# RTI-Dome-Shutter-RP2040.net
KiCad netlist of a schematic drawn in EAGLE
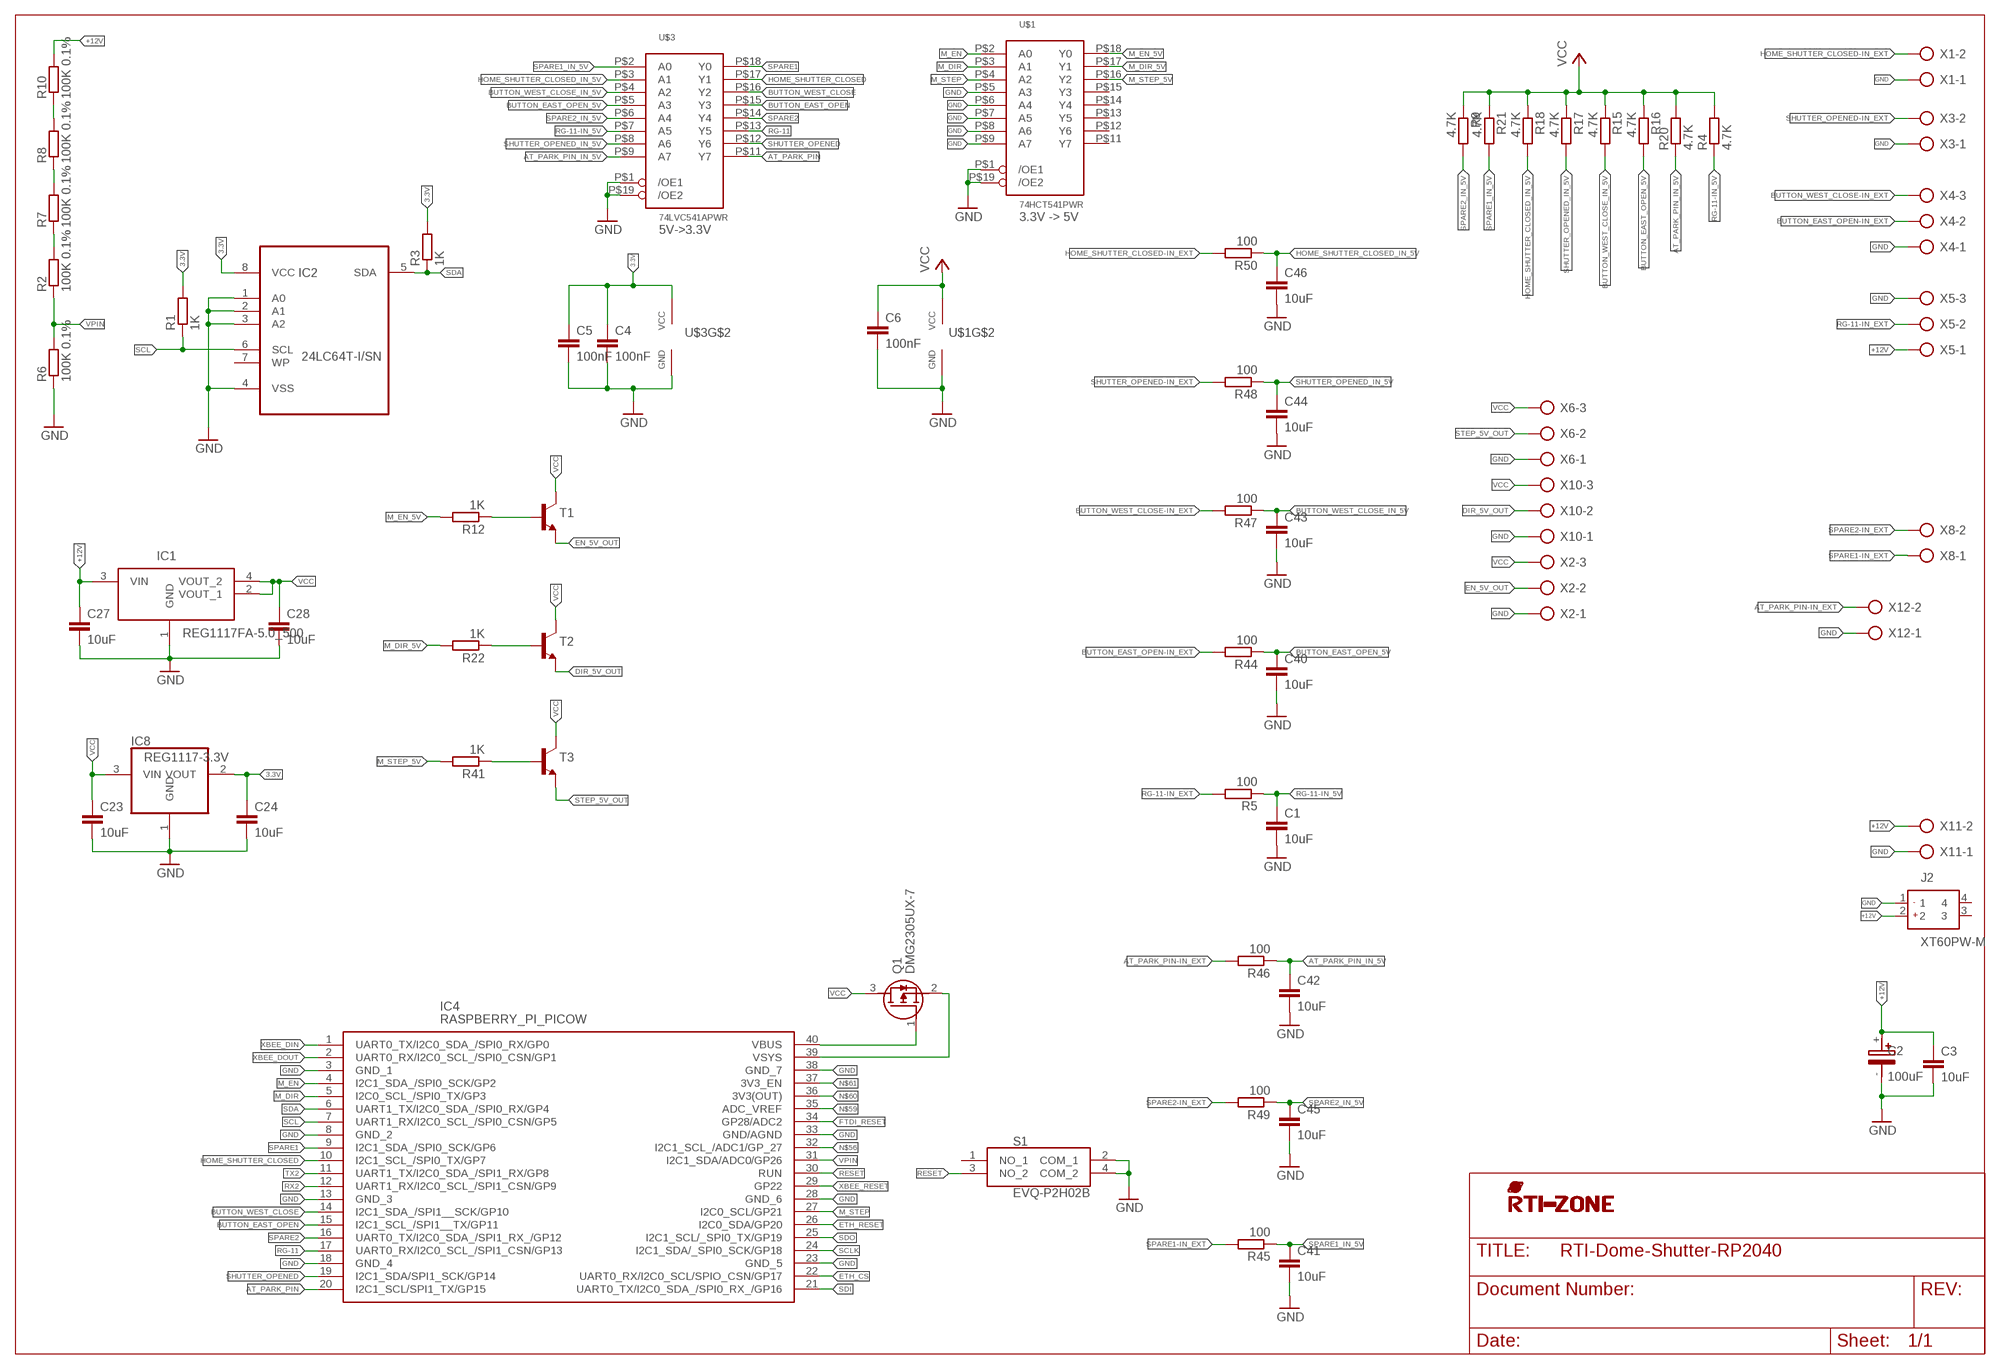
[diagram p0: schematic, sheet 1]

(export (version "E")
  (design (tool "Eeschema 10.0.6"))
  (components
    (comp (ref "C1")
      (value "10uF")
      (footprint "eagle-import:C0603")
      (fields (field (name "MPN") "CC0805KKX5R8BB106"))
      (libsource (lib "eagle-import") (part "C-EU'0603'"))
    )
    (comp (ref "C2")
      (value "100uF")
      (footprint "eagle-import:UD-10X10_NICHICON")
      (fields (field (name "MPN") "MAL215099804E3"))
      (libsource (lib "eagle-import") (part "MAL215099804E3{dblquote}{dblquote}"))
    )
    (comp (ref "C3")
      (value "10uF")
      (footprint "eagle-import:C0603")
      (fields (field (name "MPN") "CC0805KKX5R8BB106"))
      (libsource (lib "eagle-import") (part "C-EU'0603'"))
    )
    (comp (ref "C4")
      (value "100nF")
      (footprint "eagle-import:C0603")
      (fields (field (name "MPN") "0805YD104KAT2A"))
      (libsource (lib "eagle-import") (part "C-EU'0603'"))
    )
    (comp (ref "C5")
      (value "100nF")
      (footprint "eagle-import:C0603")
      (fields (field (name "MPN") "0805YD104KAT2A"))
      (libsource (lib "eagle-import") (part "C-EU'0603'"))
    )
    (comp (ref "C6")
      (value "100nF")
      (footprint "eagle-import:C0603")
      (fields (field (name "MPN") "0805YD104KAT2A"))
      (libsource (lib "eagle-import") (part "C-EU'0603'"))
    )
    (comp (ref "C23")
      (value "10uF")
      (footprint "eagle-import:C0603")
      (fields (field (name "MPN") "CC0805KKX5R8BB106"))
      (libsource (lib "eagle-import") (part "C-EU'0603'"))
    )
    (comp (ref "C24")
      (value "10uF")
      (footprint "eagle-import:C0603")
      (fields (field (name "MPN") "CC0805KKX5R8BB106"))
      (libsource (lib "eagle-import") (part "C-EU'0603'"))
    )
    (comp (ref "C27")
      (value "10uF")
      (footprint "eagle-import:C0603")
      (fields (field (name "MPN") "CC0805KKX5R8BB106"))
      (libsource (lib "eagle-import") (part "C-EU'0603'"))
    )
    (comp (ref "C28")
      (value "10uF")
      (footprint "eagle-import:C0603")
      (fields (field (name "MPN") "CC0805KKX5R8BB106"))
      (libsource (lib "eagle-import") (part "C-EU'0603'"))
    )
    (comp (ref "C40")
      (value "10uF")
      (footprint "eagle-import:C0603")
      (fields (field (name "MPN") "CC0805KKX5R8BB106"))
      (libsource (lib "eagle-import") (part "C-EU'0603'"))
    )
    (comp (ref "C41")
      (value "10uF")
      (footprint "eagle-import:C0603")
      (fields (field (name "MPN") "CC0805KKX5R8BB106"))
      (libsource (lib "eagle-import") (part "C-EU'0603'"))
    )
    (comp (ref "C42")
      (value "10uF")
      (footprint "eagle-import:C0603")
      (fields (field (name "MPN") "CC0805KKX5R8BB106"))
      (libsource (lib "eagle-import") (part "C-EU'0603'"))
    )
    (comp (ref "C43")
      (value "10uF")
      (footprint "eagle-import:C0603")
      (fields (field (name "MPN") "CC0805KKX5R8BB106"))
      (libsource (lib "eagle-import") (part "C-EU'0603'"))
    )
    (comp (ref "C44")
      (value "10uF")
      (footprint "eagle-import:C0603")
      (fields (field (name "MPN") "CC0805KKX5R8BB106"))
      (libsource (lib "eagle-import") (part "C-EU'0603'"))
    )
    (comp (ref "C45")
      (value "10uF")
      (footprint "eagle-import:C0603")
      (fields (field (name "MPN") "CC0805KKX5R8BB106"))
      (libsource (lib "eagle-import") (part "C-EU'0603'"))
    )
    (comp (ref "C46")
      (value "10uF")
      (footprint "eagle-import:C0603")
      (fields (field (name "MPN") "CC0805KKX5R8BB106"))
      (libsource (lib "eagle-import") (part "C-EU'0603'"))
    )
    (comp (ref "IC1")
      (value "REG1117FA-5.0_500")
      (footprint "eagle-import:REG1117FA50500")
      (fields
        (field (name "ARROW_PART_NUMBER") "REG1117FA-5.0/500")
        (field (name "MOUSER_PART_NUMBER") "595-REG1117FA50/500")
      )
      (libsource (lib "eagle-import") (part "REG1117FA-5.0_500"))
    )
    (comp (ref "IC2")
      (value "24LC64T-I/SN")
      (footprint "eagle-import:SOIC127P600X175-8N")
      (libsource (lib "eagle-import") (part "24LC64T-I/SN"))
    )
    (comp (ref "IC4")
      (value "RASPBERRY_PI_PICOW")
      (footprint "eagle-import:RASPBERRYPIPICO-W")
      (libsource (lib "eagle-import") (part "RASPBERRY_PI_PICOW"))
    )
    (comp (ref "IC8")
      (value "REG1117-3.3V")
      (footprint "eagle-import:SOT223")
      (fields (field (name "MPN") "REG1117") (field (name "MPN_1") "REG1117-3.3/2K5"))
      (libsource (lib "eagle-import") (part "REG1117"))
    )
    (comp (ref "J2")
      (value "XT60PW-M")
      (footprint "eagle-import:XT60PWM")
      (libsource (lib "eagle-import") (part "XT60PW-M"))
    )
    (comp (ref "Q1")
      (value "DMG2305UX-7")
      (footprint "eagle-import:SOT96P240X115-3N")
      (fields (field (name "MOUSER_PART_NUMBER") "621-DMG2305UX-7"))
      (libsource (lib "eagle-import") (part "DMG2305UX-7"))
    )
    (comp (ref "R1")
      (value "1K")
      (footprint "eagle-import:R0603")
      (fields (field (name "MPN") "RT0805FRE071KL"))
      (libsource (lib "eagle-import") (part "R-EU'0603'"))
    )
    (comp (ref "R2")
      (value "100K 0.1%")
      (footprint "eagle-import:R0603")
      (fields (field (name "MPN") "AT0805BRD07100KL"))
      (libsource (lib "eagle-import") (part "R-EU'0603'"))
    )
    (comp (ref "R3")
      (value "1K")
      (footprint "eagle-import:R0603")
      (fields (field (name "MPN") "RT0805FRE071KL"))
      (libsource (lib "eagle-import") (part "R-EU'0603'"))
    )
    (comp (ref "R4")
      (value "4.7K")
      (footprint "eagle-import:R0603")
      (fields (field (name "MPN") "RT0805FRE074K7L"))
      (libsource (lib "eagle-import") (part "R-EU'0603'"))
    )
    (comp (ref "R5")
      (value "100")
      (footprint "eagle-import:R0603")
      (fields (field (name "MPN") "RT0805FRD07100RL"))
      (libsource (lib "eagle-import") (part "R-EU'0603'"))
    )
    (comp (ref "R6")
      (value "100K 0.1%")
      (footprint "eagle-import:R0603")
      (fields (field (name "MPN") "AT0805BRD07100KL"))
      (libsource (lib "eagle-import") (part "R-EU'0603'"))
    )
    (comp (ref "R7")
      (value "100K 0.1%")
      (footprint "eagle-import:R0603")
      (fields (field (name "MPN") "AT0805BRD07100KL"))
      (libsource (lib "eagle-import") (part "R-EU'0603'"))
    )
    (comp (ref "R8")
      (value "100K 0.1%")
      (footprint "eagle-import:R0603")
      (fields (field (name "MPN") "AT0805BRD07100KL"))
      (libsource (lib "eagle-import") (part "R-EU'0603'"))
    )
    (comp (ref "R9")
      (value "4.7K")
      (footprint "eagle-import:R0603")
      (fields (field (name "MPN") "RT0805FRE074K7L"))
      (libsource (lib "eagle-import") (part "R-EU'0603'"))
    )
    (comp (ref "R10")
      (value "100K 0.1%")
      (footprint "eagle-import:R0603")
      (fields (field (name "MPN") "AT0805BRD07100KL"))
      (libsource (lib "eagle-import") (part "R-EU'0603'"))
    )
    (comp (ref "R12")
      (value "1K")
      (footprint "eagle-import:R0603")
      (fields (field (name "MPN") "RT0805FRE074K7L"))
      (libsource (lib "eagle-import") (part "R-EU'0603'"))
    )
    (comp (ref "R15")
      (value "4.7K")
      (footprint "eagle-import:R0603")
      (fields (field (name "MPN") "RT0805FRE074K7L"))
      (libsource (lib "eagle-import") (part "R-EU'0603'"))
    )
    (comp (ref "R16")
      (value "4.7K")
      (footprint "eagle-import:R0603")
      (fields (field (name "MPN") "RT0805FRE074K7L"))
      (libsource (lib "eagle-import") (part "R-EU'0603'"))
    )
    (comp (ref "R17")
      (value "4.7K")
      (footprint "eagle-import:R0603")
      (fields (field (name "MPN") "RT0805FRE074K7L"))
      (libsource (lib "eagle-import") (part "R-EU'0603'"))
    )
    (comp (ref "R18")
      (value "4.7K")
      (footprint "eagle-import:R0603")
      (fields (field (name "MPN") "RT0805FRE074K7L"))
      (libsource (lib "eagle-import") (part "R-EU'0603'"))
    )
    (comp (ref "R20")
      (value "4.7K")
      (footprint "eagle-import:R0603")
      (fields (field (name "MPN") "RT0805FRE074K7L"))
      (libsource (lib "eagle-import") (part "R-EU'0603'"))
    )
    (comp (ref "R21")
      (value "4.7K")
      (footprint "eagle-import:R0603")
      (fields (field (name "MPN") "RT0805FRE074K7L"))
      (libsource (lib "eagle-import") (part "R-EU'0603'"))
    )
    (comp (ref "R22")
      (value "1K")
      (footprint "eagle-import:R0603")
      (fields (field (name "MPN") "RT0805FRE074K7L"))
      (libsource (lib "eagle-import") (part "R-EU'0603'"))
    )
    (comp (ref "R41")
      (value "1K")
      (footprint "eagle-import:R0603")
      (fields (field (name "MPN") "RT0805FRE074K7L"))
      (libsource (lib "eagle-import") (part "R-EU'0603'"))
    )
    (comp (ref "R44")
      (value "100")
      (footprint "eagle-import:R0603")
      (fields (field (name "MPN") "RT0805FRD07100RL"))
      (libsource (lib "eagle-import") (part "R-EU'0603'"))
    )
    (comp (ref "R45")
      (value "100")
      (footprint "eagle-import:R0603")
      (fields (field (name "MPN") "RT0805FRD07100RL"))
      (libsource (lib "eagle-import") (part "R-EU'0603'"))
    )
    (comp (ref "R46")
      (value "100")
      (footprint "eagle-import:R0603")
      (fields (field (name "MPN") "RT0805FRD07100RL"))
      (libsource (lib "eagle-import") (part "R-EU'0603'"))
    )
    (comp (ref "R47")
      (value "100")
      (footprint "eagle-import:R0603")
      (fields (field (name "MPN") "RT0805FRD07100RL"))
      (libsource (lib "eagle-import") (part "R-EU'0603'"))
    )
    (comp (ref "R48")
      (value "100")
      (footprint "eagle-import:R0603")
      (fields (field (name "MPN") "RT0805FRD07100RL"))
      (libsource (lib "eagle-import") (part "R-EU'0603'"))
    )
    (comp (ref "R49")
      (value "100")
      (footprint "eagle-import:R0603")
      (fields (field (name "MPN") "RT0805FRD07100RL"))
      (libsource (lib "eagle-import") (part "R-EU'0603'"))
    )
    (comp (ref "R50")
      (value "100")
      (footprint "eagle-import:R0603")
      (fields (field (name "MPN") "RT0805FRD07100RL"))
      (libsource (lib "eagle-import") (part "R-EU'0603'"))
    )
    (comp (ref "S1")
      (value "EVQ-P2H02B")
      (footprint "eagle-import:EVQP2H02B")
      (fields (field (name "MOUSER_PART_NUMBER") "667-EVQ-P2H02B"))
      (libsource (lib "eagle-import") (part "EVQ-P2H02B"))
    )
    (comp (ref "T1")
      (value "MMBT3904LT1-NPN-SOT23-BEC")
      (footprint "eagle-import:SOT23-BEC")
      (libsource (lib "eagle-import") (part "-NPN-SOT23-BECMMBT3904LT1"))
    )
    (comp (ref "T2")
      (value "MMBT3904LT1-NPN-SOT23-BEC")
      (footprint "eagle-import:SOT23-BEC")
      (libsource (lib "eagle-import") (part "-NPN-SOT23-BECMMBT3904LT1"))
    )
    (comp (ref "T3")
      (value "MMBT3904LT1-NPN-SOT23-BEC")
      (footprint "eagle-import:SOT23-BEC")
      (libsource (lib "eagle-import") (part "-NPN-SOT23-BECMMBT3904LT1"))
    )
    (comp (ref "U$1")
      (value "74HCT541PWR")
      (footprint "eagle-import:TSSOP20")
      (libsource (lib "eagle-import") (part "74541B"))
    )
    (comp (ref "U$3")
      (value "74LVC541APWR")
      (footprint "eagle-import:TSSOP20")
      (libsource (lib "eagle-import") (part "74541B"))
    )
    (comp (ref "U$4")
      (value "RTI-LOGO_BIG")
      (footprint "eagle-import:LOGO_BIG")
      (libsource (lib "eagle-import") (part "RTI-LOGO_BIG"))
    )
    (comp (ref "X1")
      (value "AK500/2")
      (footprint "eagle-import:AK500_2")
      (fields (field (name "MPN") "691101710002"))
      (libsource (lib "eagle-import") (part "AK500/2"))
    )
    (comp (ref "X2")
      (value "AK500/3")
      (footprint "eagle-import:AK500_3")
      (libsource (lib "eagle-import") (part "AK500/3"))
    )
    (comp (ref "X3")
      (value "AK500/2")
      (footprint "eagle-import:AK500_2")
      (fields (field (name "MPN") "691101710002"))
      (libsource (lib "eagle-import") (part "AK500/2"))
    )
    (comp (ref "X4")
      (value "AK500/3")
      (footprint "eagle-import:AK500_3")
      (fields (field (name "MPN") "691101710003"))
      (libsource (lib "eagle-import") (part "AK500/3"))
    )
    (comp (ref "X5")
      (value "AK500/3")
      (footprint "eagle-import:AK500_3")
      (fields (field (name "MPN") "691101710003"))
      (libsource (lib "eagle-import") (part "AK500/3"))
    )
    (comp (ref "X6")
      (value "AK500/3")
      (footprint "eagle-import:AK500_3")
      (libsource (lib "eagle-import") (part "AK500/3"))
    )
    (comp (ref "X8")
      (value "AK500/2")
      (footprint "eagle-import:AK500_2")
      (fields (field (name "MPN") "691101710002"))
      (libsource (lib "eagle-import") (part "AK500/2"))
    )
    (comp (ref "X10")
      (value "AK500/3")
      (footprint "eagle-import:AK500_3")
      (libsource (lib "eagle-import") (part "AK500/3"))
    )
    (comp (ref "X11")
      (value "AK500/2")
      (footprint "eagle-import:AK500_2")
      (fields (field (name "MPN") "691101710002"))
      (libsource (lib "eagle-import") (part "AK500/2"))
    )
    (comp (ref "X12")
      (value "AK500/2")
      (footprint "eagle-import:AK500_2")
      (fields (field (name "MPN") "691101710002"))
      (libsource (lib "eagle-import") (part "AK500/2"))
    )
  )
  (nets
    (net (code "1") (name "+12V") (class "Default")
      (node (ref "C2") (pin "+") (pinfunction "+_+") (pintype "bidirectional"))
      (node (ref "C27") (pin "1") (pinfunction "1_1") (pintype "passive"))
      (node (ref "C3") (pin "1") (pinfunction "1_1") (pintype "passive"))
      (node (ref "IC1") (pin "3") (pinfunction "VIN_3") (pintype "bidirectional"))
      (node (ref "J2") (pin "2") (pinfunction "2_2") (pintype "bidirectional"))
      (node (ref "R10") (pin "2") (pinfunction "2_2") (pintype "passive"))
      (node (ref "X11") (pin "2") (pinfunction "KL_2") (pintype "passive"))
      (node (ref "X5") (pin "1") (pinfunction "KL_1") (pintype "passive"))
    )
    (net (code "2") (name "3.3V") (class "Default")
      (node (ref "C24") (pin "1") (pinfunction "1_1") (pintype "passive"))
      (node (ref "C4") (pin "1") (pinfunction "1_1") (pintype "passive"))
      (node (ref "C5") (pin "1") (pinfunction "1_1") (pintype "passive"))
      (node (ref "IC2") (pin "8") (pinfunction "VCC_8") (pintype "power_in"))
      (node (ref "IC8") (pin "2") (pinfunction "VOUT_2") (pintype "output"))
      (node (ref "R1") (pin "2") (pinfunction "2_2") (pintype "passive"))
      (node (ref "R3") (pin "2") (pinfunction "2_2") (pintype "passive"))
      (node (ref "U$3") (pin "P$20") (pinfunction "VCC_P$20") (pintype "power_in"))
    )
    (net (code "3") (name "AT_PARK_PIN") (class "Default")
      (node (ref "IC4") (pin "20") (pinfunction "I2C1_SCL/SPI1_TX/GP15_20") (pintype "bidirectional"))
      (node (ref "U$3") (pin "P$11") (pinfunction "Y7_P$11") (pintype "output"))
    )
    (net (code "4") (name "AT_PARK_PIN-IN_EXT") (class "Default")
      (node (ref "R46") (pin "2") (pinfunction "2_2") (pintype "passive"))
      (node (ref "X12") (pin "2") (pinfunction "KL_2") (pintype "passive"))
    )
    (net (code "5") (name "AT_PARK_PIN_IN_5V") (class "Default")
      (node (ref "C42") (pin "1") (pinfunction "1_1") (pintype "passive"))
      (node (ref "R20") (pin "1") (pinfunction "1_1") (pintype "passive"))
      (node (ref "R46") (pin "1") (pinfunction "1_1") (pintype "passive"))
      (node (ref "U$3") (pin "P$9") (pinfunction "A7_P$9") (pintype "input"))
    )
    (net (code "6") (name "BUTTON_EAST_OPEN") (class "Default")
      (node (ref "IC4") (pin "15") (pinfunction "I2C1_SCL_/SPI1__TX/GP11_15") (pintype "bidirectional"))
      (node (ref "U$3") (pin "P$15") (pinfunction "Y3_P$15") (pintype "output"))
    )
    (net (code "7") (name "BUTTON_EAST_OPEN-IN_EXT") (class "Default")
      (node (ref "R44") (pin "2") (pinfunction "2_2") (pintype "passive"))
      (node (ref "X4") (pin "2") (pinfunction "KL_2") (pintype "passive"))
    )
    (net (code "8") (name "BUTTON_EAST_OPEN_5V") (class "Default")
      (node (ref "C40") (pin "1") (pinfunction "1_1") (pintype "passive"))
      (node (ref "R16") (pin "2") (pinfunction "2_2") (pintype "passive"))
      (node (ref "R44") (pin "1") (pinfunction "1_1") (pintype "passive"))
      (node (ref "U$3") (pin "P$5") (pinfunction "A3_P$5") (pintype "input"))
    )
    (net (code "9") (name "BUTTON_WEST_CLOSE") (class "Default")
      (node (ref "IC4") (pin "14") (pinfunction "I2C1_SDA_/SPI1__SCK/GP10_14") (pintype "bidirectional"))
      (node (ref "U$3") (pin "P$16") (pinfunction "Y2_P$16") (pintype "output"))
    )
    (net (code "10") (name "BUTTON_WEST_CLOSE-IN_EXT") (class "Default")
      (node (ref "R47") (pin "2") (pinfunction "2_2") (pintype "passive"))
      (node (ref "X4") (pin "3") (pinfunction "KL_3") (pintype "passive"))
    )
    (net (code "11") (name "BUTTON_WEST_CLOSE_IN_5V") (class "Default")
      (node (ref "C43") (pin "1") (pinfunction "1_1") (pintype "passive"))
      (node (ref "R15") (pin "2") (pinfunction "2_2") (pintype "passive"))
      (node (ref "R47") (pin "1") (pinfunction "1_1") (pintype "passive"))
      (node (ref "U$3") (pin "P$4") (pinfunction "A2_P$4") (pintype "input"))
    )
    (net (code "12") (name "DIR_5V_OUT") (class "Default")
      (node (ref "T2") (pin "E") (pinfunction "E_E") (pintype "passive"))
      (node (ref "X10") (pin "2") (pinfunction "KL_2") (pintype "passive"))
    )
    (net (code "13") (name "EN_5V_OUT") (class "Default")
      (node (ref "T1") (pin "E") (pinfunction "E_E") (pintype "passive"))
      (node (ref "X2") (pin "2") (pinfunction "KL_2") (pintype "passive"))
    )
    (net (code "14") (name "ETH_CS") (class "Default")
      (node (ref "IC4") (pin "22") (pinfunction "UART0_RX/I2C0_SCL/SPIO_CSN/GP17_22") (pintype "bidirectional"))
    )
    (net (code "15") (name "ETH_RESET") (class "Default")
      (node (ref "IC4") (pin "26") (pinfunction "I2C0_SDA/GP20_26") (pintype "bidirectional"))
    )
    (net (code "16") (name "FTDI_RESET") (class "Default")
      (node (ref "IC4") (pin "34") (pinfunction "GP28/ADC2_34") (pintype "bidirectional"))
    )
    (net (code "17") (name "GND") (class "Default")
      (node (ref "C1") (pin "2") (pinfunction "2_2") (pintype "passive"))
      (node (ref "C2") (pin "-") (pinfunction "-_-") (pintype "bidirectional"))
      (node (ref "C23") (pin "2") (pinfunction "2_2") (pintype "passive"))
      (node (ref "C24") (pin "2") (pinfunction "2_2") (pintype "passive"))
      (node (ref "C27") (pin "2") (pinfunction "2_2") (pintype "passive"))
      (node (ref "C28") (pin "2") (pinfunction "2_2") (pintype "passive"))
      (node (ref "C3") (pin "2") (pinfunction "2_2") (pintype "passive"))
      (node (ref "C4") (pin "2") (pinfunction "2_2") (pintype "passive"))
      (node (ref "C40") (pin "2") (pinfunction "2_2") (pintype "passive"))
      (node (ref "C41") (pin "2") (pinfunction "2_2") (pintype "passive"))
      (node (ref "C42") (pin "2") (pinfunction "2_2") (pintype "passive"))
      (node (ref "C43") (pin "2") (pinfunction "2_2") (pintype "passive"))
      (node (ref "C44") (pin "2") (pinfunction "2_2") (pintype "passive"))
      (node (ref "C45") (pin "2") (pinfunction "2_2") (pintype "passive"))
      (node (ref "C46") (pin "2") (pinfunction "2_2") (pintype "passive"))
      (node (ref "C5") (pin "2") (pinfunction "2_2") (pintype "passive"))
      (node (ref "C6") (pin "2") (pinfunction "2_2") (pintype "passive"))
      (node (ref "IC1") (pin "1") (pinfunction "GND_1") (pintype "bidirectional"))
      (node (ref "IC2") (pin "1") (pinfunction "A0_1") (pintype "input"))
      (node (ref "IC2") (pin "2") (pinfunction "A1_2") (pintype "input"))
      (node (ref "IC2") (pin "3") (pinfunction "A2_3") (pintype "input"))
      (node (ref "IC2") (pin "4") (pinfunction "VSS_4") (pintype "passive"))
      (node (ref "IC4") (pin "13") (pinfunction "GND_3_13") (pintype "bidirectional"))
      (node (ref "IC4") (pin "18") (pinfunction "GND_4_18") (pintype "bidirectional"))
      (node (ref "IC4") (pin "23") (pinfunction "GND_5_23") (pintype "bidirectional"))
      (node (ref "IC4") (pin "28") (pinfunction "GND_6_28") (pintype "bidirectional"))
      (node (ref "IC4") (pin "3") (pinfunction "GND_1_3") (pintype "bidirectional"))
      (node (ref "IC4") (pin "33") (pinfunction "GND/AGND_33") (pintype "bidirectional"))
      (node (ref "IC4") (pin "38") (pinfunction "GND_7_38") (pintype "bidirectional"))
      (node (ref "IC4") (pin "8") (pinfunction "GND_2_8") (pintype "bidirectional"))
      (node (ref "IC8") (pin "1") (pinfunction "GND_1") (pintype "power_in"))
      (node (ref "J2") (pin "1") (pinfunction "1_1") (pintype "bidirectional"))
      (node (ref "R6") (pin "1") (pinfunction "1_1") (pintype "passive"))
      (node (ref "S1") (pin "2") (pinfunction "COM_1_2") (pintype "bidirectional"))
      (node (ref "S1") (pin "4") (pinfunction "COM_2_4") (pintype "bidirectional"))
      (node (ref "U$1") (pin "P$1") (pinfunction "/OE1_P$1") (pintype "input"))
      (node (ref "U$1") (pin "P$10") (pinfunction "GND_P$10") (pintype "power_in"))
      (node (ref "U$1") (pin "P$19") (pinfunction "/OE2_P$19") (pintype "input"))
      (node (ref "U$1") (pin "P$5") (pinfunction "A3_P$5") (pintype "input"))
      (node (ref "U$1") (pin "P$6") (pinfunction "A4_P$6") (pintype "input"))
      (node (ref "U$1") (pin "P$7") (pinfunction "A5_P$7") (pintype "input"))
      (node (ref "U$1") (pin "P$8") (pinfunction "A6_P$8") (pintype "input"))
      (node (ref "U$1") (pin "P$9") (pinfunction "A7_P$9") (pintype "input"))
      (node (ref "U$3") (pin "P$1") (pinfunction "/OE1_P$1") (pintype "input"))
      (node (ref "U$3") (pin "P$10") (pinfunction "GND_P$10") (pintype "power_in"))
      (node (ref "U$3") (pin "P$19") (pinfunction "/OE2_P$19") (pintype "input"))
      (node (ref "X1") (pin "1") (pinfunction "KL_1") (pintype "passive"))
      (node (ref "X10") (pin "1") (pinfunction "KL_1") (pintype "passive"))
      (node (ref "X11") (pin "1") (pinfunction "KL_1") (pintype "passive"))
      (node (ref "X12") (pin "1") (pinfunction "KL_1") (pintype "passive"))
      (node (ref "X2") (pin "1") (pinfunction "KL_1") (pintype "passive"))
      (node (ref "X3") (pin "1") (pinfunction "KL_1") (pintype "passive"))
      (node (ref "X4") (pin "1") (pinfunction "KL_1") (pintype "passive"))
      (node (ref "X5") (pin "3") (pinfunction "KL_3") (pintype "passive"))
      (node (ref "X6") (pin "1") (pinfunction "KL_1") (pintype "passive"))
    )
    (net (code "18") (name "HOME_SHUTTER_CLOSED") (class "Default")
      (node (ref "IC4") (pin "10") (pinfunction "I2C1_SCL_/SPI0_TX/GP7_10") (pintype "bidirectional"))
      (node (ref "U$3") (pin "P$17") (pinfunction "Y1_P$17") (pintype "output"))
    )
    (net (code "19") (name "HOME_SHUTTER_CLOSED-IN_EXT") (class "Default")
      (node (ref "R50") (pin "2") (pinfunction "2_2") (pintype "passive"))
      (node (ref "X1") (pin "2") (pinfunction "KL_2") (pintype "passive"))
    )
    (net (code "20") (name "HOME_SHUTTER_CLOSED_IN_5V") (class "Default")
      (node (ref "C46") (pin "1") (pinfunction "1_1") (pintype "passive"))
      (node (ref "R18") (pin "2") (pinfunction "2_2") (pintype "passive"))
      (node (ref "R50") (pin "1") (pinfunction "1_1") (pintype "passive"))
      (node (ref "U$3") (pin "P$3") (pinfunction "A1_P$3") (pintype "input"))
    )
    (net (code "21") (name "M_DIR") (class "Default")
      (node (ref "IC4") (pin "5") (pinfunction "I2C0_SCL_/SPI0_TX/GP3_5") (pintype "bidirectional"))
      (node (ref "U$1") (pin "P$3") (pinfunction "A1_P$3") (pintype "input"))
    )
    (net (code "22") (name "M_DIR_5V") (class "Default")
      (node (ref "R22") (pin "2") (pinfunction "2_2") (pintype "passive"))
      (node (ref "U$1") (pin "P$17") (pinfunction "Y1_P$17") (pintype "output"))
    )
    (net (code "23") (name "M_EN") (class "Default")
      (node (ref "IC4") (pin "4") (pinfunction "I2C1_SDA_/SPI0_SCK/GP2_4") (pintype "bidirectional"))
      (node (ref "U$1") (pin "P$2") (pinfunction "A0_P$2") (pintype "input"))
    )
    (net (code "24") (name "M_EN_5V") (class "Default")
      (node (ref "R12") (pin "2") (pinfunction "2_2") (pintype "passive"))
      (node (ref "U$1") (pin "P$18") (pinfunction "Y0_P$18") (pintype "output"))
    )
    (net (code "25") (name "M_STEP") (class "Default")
      (node (ref "IC4") (pin "27") (pinfunction "I2C0_SCL/GP21_27") (pintype "bidirectional"))
      (node (ref "U$1") (pin "P$4") (pinfunction "A2_P$4") (pintype "input"))
    )
    (net (code "26") (name "M_STEP_5V") (class "Default")
      (node (ref "R41") (pin "2") (pinfunction "2_2") (pintype "passive"))
      (node (ref "U$1") (pin "P$16") (pinfunction "Y2_P$16") (pintype "output"))
    )
    (net (code "27") (name "N$56") (class "Default")
      (node (ref "IC4") (pin "32") (pinfunction "I2C1_SCL_/ADC1/GP_27_32") (pintype "bidirectional"))
    )
    (net (code "28") (name "N$59") (class "Default")
      (node (ref "IC4") (pin "35") (pinfunction "ADC_VREF_35") (pintype "bidirectional"))
    )
    (net (code "29") (name "N$60") (class "Default")
      (node (ref "IC4") (pin "36") (pinfunction "3V3(OUT)_36") (pintype "bidirectional"))
    )
    (net (code "30") (name "N$61") (class "Default")
      (node (ref "IC4") (pin "37") (pinfunction "3V3_EN_37") (pintype "bidirectional"))
    )
    (net (code "31") (name "Net-(IC4-VBUS)") (class "Default")
      (node (ref "IC4") (pin "40") (pinfunction "VBUS_40") (pintype "bidirectional"))
      (node (ref "Q1") (pin "1") (pinfunction "G_1") (pintype "bidirectional"))
    )
    (net (code "32") (name "Net-(IC4-VSYS)") (class "Default")
      (node (ref "IC4") (pin "39") (pinfunction "VSYS_39") (pintype "bidirectional"))
      (node (ref "Q1") (pin "2") (pinfunction "S_2") (pintype "bidirectional"))
    )
    (net (code "33") (name "Net-(R2-Pad2)") (class "Default")
      (node (ref "R2") (pin "2") (pinfunction "2_2") (pintype "passive"))
      (node (ref "R7") (pin "1") (pinfunction "1_1") (pintype "passive"))
    )
    (net (code "34") (name "Net-(R7-Pad2)") (class "Default")
      (node (ref "R7") (pin "2") (pinfunction "2_2") (pintype "passive"))
      (node (ref "R8") (pin "1") (pinfunction "1_1") (pintype "passive"))
    )
    (net (code "35") (name "Net-(R10-Pad1)") (class "Default")
      (node (ref "R10") (pin "1") (pinfunction "1_1") (pintype "passive"))
      (node (ref "R8") (pin "2") (pinfunction "2_2") (pintype "passive"))
    )
    (net (code "36") (name "Net-(R12-Pad1)") (class "Default")
      (node (ref "R12") (pin "1") (pinfunction "1_1") (pintype "passive"))
      (node (ref "T1") (pin "B") (pinfunction "B_B") (pintype "passive"))
    )
    (net (code "37") (name "Net-(R22-Pad1)") (class "Default")
      (node (ref "R22") (pin "1") (pinfunction "1_1") (pintype "passive"))
      (node (ref "T2") (pin "B") (pinfunction "B_B") (pintype "passive"))
    )
    (net (code "38") (name "Net-(R41-Pad1)") (class "Default")
      (node (ref "R41") (pin "1") (pinfunction "1_1") (pintype "passive"))
      (node (ref "T3") (pin "B") (pinfunction "B_B") (pintype "passive"))
    )
    (net (code "39") (name "RESET") (class "Default")
      (node (ref "IC4") (pin "30") (pinfunction "RUN_30") (pintype "bidirectional"))
      (node (ref "S1") (pin "3") (pinfunction "NO_2_3") (pintype "bidirectional"))
    )
    (net (code "40") (name "RG-11") (class "Default")
      (node (ref "IC4") (pin "17") (pinfunction "UART0_RX/I2C0_SCL_/SPI1_CSN/GP13_17") (pintype "bidirectional"))
      (node (ref "U$3") (pin "P$13") (pinfunction "Y5_P$13") (pintype "output"))
    )
    (net (code "41") (name "RG-11-IN_5V") (class "Default")
      (node (ref "C1") (pin "1") (pinfunction "1_1") (pintype "passive"))
      (node (ref "R4") (pin "1") (pinfunction "1_1") (pintype "passive"))
      (node (ref "R5") (pin "1") (pinfunction "1_1") (pintype "passive"))
      (node (ref "U$3") (pin "P$7") (pinfunction "A5_P$7") (pintype "input"))
    )
    (net (code "42") (name "RG-11-IN_EXT") (class "Default")
      (node (ref "R5") (pin "2") (pinfunction "2_2") (pintype "passive"))
      (node (ref "X5") (pin "2") (pinfunction "KL_2") (pintype "passive"))
    )
    (net (code "43") (name "RX2") (class "Default")
      (node (ref "IC4") (pin "12") (pinfunction "UART1_RX/I2C0_SCL_/SPI1_CSN/GP9_12") (pintype "bidirectional"))
    )
    (net (code "44") (name "SCL") (class "Default")
      (node (ref "IC2") (pin "6") (pinfunction "SCL_6") (pintype "input"))
      (node (ref "IC4") (pin "7") (pinfunction "UART1_RX/I2C0_SCL_/SPI0_CSN/GP5_7") (pintype "bidirectional"))
      (node (ref "R1") (pin "1") (pinfunction "1_1") (pintype "passive"))
    )
    (net (code "45") (name "SCLK") (class "Default")
      (node (ref "IC4") (pin "24") (pinfunction "I2C1_SDA/_SPI0_SCK/GP18_24") (pintype "bidirectional"))
    )
    (net (code "46") (name "SDA") (class "Default")
      (node (ref "IC2") (pin "5") (pinfunction "SDA_5") (pintype "bidirectional"))
      (node (ref "IC4") (pin "6") (pinfunction "UART1_TX/I2C0_SDA_/SPI0_RX/GP4_6") (pintype "bidirectional"))
      (node (ref "R3") (pin "1") (pinfunction "1_1") (pintype "passive"))
    )
    (net (code "47") (name "SDI") (class "Default")
      (node (ref "IC4") (pin "21") (pinfunction "UART0_TX/I2C0_SDA_/SPI0_RX_/GP16_21") (pintype "bidirectional"))
    )
    (net (code "48") (name "SDO") (class "Default")
      (node (ref "IC4") (pin "25") (pinfunction "I2C1_SCL/_SPI0_TX/GP19_25") (pintype "bidirectional"))
    )
    (net (code "49") (name "SHUTTER_OPENED") (class "Default")
      (node (ref "IC4") (pin "19") (pinfunction "I2C1_SDA/SPI1_SCK/GP14_19") (pintype "bidirectional"))
      (node (ref "U$3") (pin "P$12") (pinfunction "Y6_P$12") (pintype "output"))
    )
    (net (code "50") (name "SHUTTER_OPENED-IN_EXT") (class "Default")
      (node (ref "R48") (pin "2") (pinfunction "2_2") (pintype "passive"))
      (node (ref "X3") (pin "2") (pinfunction "KL_2") (pintype "passive"))
    )
    (net (code "51") (name "SHUTTER_OPENED_IN_5V") (class "Default")
      (node (ref "C44") (pin "1") (pinfunction "1_1") (pintype "passive"))
      (node (ref "R17") (pin "2") (pinfunction "2_2") (pintype "passive"))
      (node (ref "R48") (pin "1") (pinfunction "1_1") (pintype "passive"))
      (node (ref "U$3") (pin "P$8") (pinfunction "A6_P$8") (pintype "input"))
    )
    (net (code "52") (name "SPARE1") (class "Default")
      (node (ref "IC4") (pin "9") (pinfunction "I2C1_SDA_/SPI0_SCK/GP6_9") (pintype "bidirectional"))
      (node (ref "U$3") (pin "P$18") (pinfunction "Y0_P$18") (pintype "output"))
    )
    (net (code "53") (name "SPARE1-IN_EXT") (class "Default")
      (node (ref "R45") (pin "2") (pinfunction "2_2") (pintype "passive"))
      (node (ref "X8") (pin "1") (pinfunction "KL_1") (pintype "passive"))
    )
    (net (code "54") (name "SPARE1_IN_5V") (class "Default")
      (node (ref "C41") (pin "1") (pinfunction "1_1") (pintype "passive"))
      (node (ref "R21") (pin "2") (pinfunction "2_2") (pintype "passive"))
      (node (ref "R45") (pin "1") (pinfunction "1_1") (pintype "passive"))
      (node (ref "U$3") (pin "P$2") (pinfunction "A0_P$2") (pintype "input"))
    )
    (net (code "55") (name "SPARE2") (class "Default")
      (node (ref "IC4") (pin "16") (pinfunction "UART0_TX/I2C0_SDA_/SPI1_RX_/GP12_16") (pintype "bidirectional"))
      (node (ref "U$3") (pin "P$14") (pinfunction "Y4_P$14") (pintype "output"))
    )
    (net (code "56") (name "SPARE2-IN_EXT") (class "Default")
      (node (ref "R49") (pin "2") (pinfunction "2_2") (pintype "passive"))
      (node (ref "X8") (pin "2") (pinfunction "KL_2") (pintype "passive"))
    )
    (net (code "57") (name "SPARE2_IN_5V") (class "Default")
      (node (ref "C45") (pin "1") (pinfunction "1_1") (pintype "passive"))
      (node (ref "R49") (pin "1") (pinfunction "1_1") (pintype "passive"))
      (node (ref "R9") (pin "2") (pinfunction "2_2") (pintype "passive"))
      (node (ref "U$3") (pin "P$6") (pinfunction "A4_P$6") (pintype "input"))
    )
    (net (code "58") (name "STEP_5V_OUT") (class "Default")
      (node (ref "T3") (pin "E") (pinfunction "E_E") (pintype "passive"))
      (node (ref "X6") (pin "2") (pinfunction "KL_2") (pintype "passive"))
    )
    (net (code "59") (name "TX2") (class "Default")
      (node (ref "IC4") (pin "11") (pinfunction "UART1_TX/I2C0_SDA_/SPI1_RX/GP8_11") (pintype "bidirectional"))
    )
    (net (code "60") (name "VCC") (class "Default")
      (node (ref "C23") (pin "1") (pinfunction "1_1") (pintype "passive"))
      (node (ref "C28") (pin "1") (pinfunction "1_1") (pintype "passive"))
      (node (ref "C6") (pin "1") (pinfunction "1_1") (pintype "passive"))
      (node (ref "IC1") (pin "2") (pinfunction "VOUT_1_2") (pintype "bidirectional"))
      (node (ref "IC1") (pin "4") (pinfunction "VOUT_2_4") (pintype "bidirectional"))
      (node (ref "IC8") (pin "3") (pinfunction "VIN_3") (pintype "input"))
      (node (ref "Q1") (pin "3") (pinfunction "D_3") (pintype "bidirectional"))
      (node (ref "R15") (pin "1") (pinfunction "1_1") (pintype "passive"))
      (node (ref "R16") (pin "1") (pinfunction "1_1") (pintype "passive"))
      (node (ref "R17") (pin "1") (pinfunction "1_1") (pintype "passive"))
      (node (ref "R18") (pin "1") (pinfunction "1_1") (pintype "passive"))
      (node (ref "R20") (pin "2") (pinfunction "2_2") (pintype "passive"))
      (node (ref "R21") (pin "1") (pinfunction "1_1") (pintype "passive"))
      (node (ref "R4") (pin "2") (pinfunction "2_2") (pintype "passive"))
      (node (ref "R9") (pin "1") (pinfunction "1_1") (pintype "passive"))
      (node (ref "T1") (pin "C") (pinfunction "C_C") (pintype "passive"))
      (node (ref "T2") (pin "C") (pinfunction "C_C") (pintype "passive"))
      (node (ref "T3") (pin "C") (pinfunction "C_C") (pintype "passive"))
      (node (ref "U$1") (pin "P$20") (pinfunction "VCC_P$20") (pintype "power_in"))
      (node (ref "X10") (pin "3") (pinfunction "KL_3") (pintype "passive"))
      (node (ref "X2") (pin "3") (pinfunction "KL_3") (pintype "passive"))
      (node (ref "X6") (pin "3") (pinfunction "KL_3") (pintype "passive"))
    )
    (net (code "61") (name "VPIN") (class "Default")
      (node (ref "IC4") (pin "31") (pinfunction "I2C1_SDA/ADC0/GP26_31") (pintype "bidirectional"))
      (node (ref "R2") (pin "1") (pinfunction "1_1") (pintype "passive"))
      (node (ref "R6") (pin "2") (pinfunction "2_2") (pintype "passive"))
    )
    (net (code "62") (name "XBEE_DIN") (class "Default")
      (node (ref "IC4") (pin "1") (pinfunction "UART0_TX/I2C0_SDA_/SPI0_RX/GP0_1") (pintype "bidirectional"))
    )
    (net (code "63") (name "XBEE_DOUT") (class "Default")
      (node (ref "IC4") (pin "2") (pinfunction "UART0_RX/I2C0_SCL_/SPI0_CSN/GP1_2") (pintype "bidirectional"))
    )
    (net (code "64") (name "XBEE_RESET") (class "Default")
      (node (ref "IC4") (pin "29") (pinfunction "GP22_29") (pintype "bidirectional"))
    )
    (net (code "65") (name "unconnected-(IC2-WP-Pad7)") (class "Default")
      (node (ref "IC2") (pin "7") (pinfunction "WP_7") (pintype "input"))
    )
    (net (code "66") (name "unconnected-(J2-Pad3)") (class "Default")
      (node (ref "J2") (pin "3") (pinfunction "3_3") (pintype "bidirectional"))
    )
    (net (code "67") (name "unconnected-(J2-Pad4)") (class "Default")
      (node (ref "J2") (pin "4") (pinfunction "4_4") (pintype "bidirectional"))
    )
    (net (code "68") (name "unconnected-(S1-NO_1-Pad1)") (class "Default")
      (node (ref "S1") (pin "1") (pinfunction "NO_1_1") (pintype "bidirectional"))
    )
    (net (code "69") (name "unconnected-(U$1A-Y3-PadP$15)") (class "Default")
      (node (ref "U$1") (pin "P$15") (pinfunction "Y3_P$15") (pintype "output"))
    )
    (net (code "70") (name "unconnected-(U$1A-Y4-PadP$14)") (class "Default")
      (node (ref "U$1") (pin "P$14") (pinfunction "Y4_P$14") (pintype "output"))
    )
    (net (code "71") (name "unconnected-(U$1A-Y5-PadP$13)") (class "Default")
      (node (ref "U$1") (pin "P$13") (pinfunction "Y5_P$13") (pintype "output"))
    )
    (net (code "72") (name "unconnected-(U$1A-Y6-PadP$12)") (class "Default")
      (node (ref "U$1") (pin "P$12") (pinfunction "Y6_P$12") (pintype "output"))
    )
    (net (code "73") (name "unconnected-(U$1A-Y7-PadP$11)") (class "Default")
      (node (ref "U$1") (pin "P$11") (pinfunction "Y7_P$11") (pintype "output"))
    )
  )
)
